# Power_Supply.net
KiCad netlist of a schematic drawn in Altium Designer
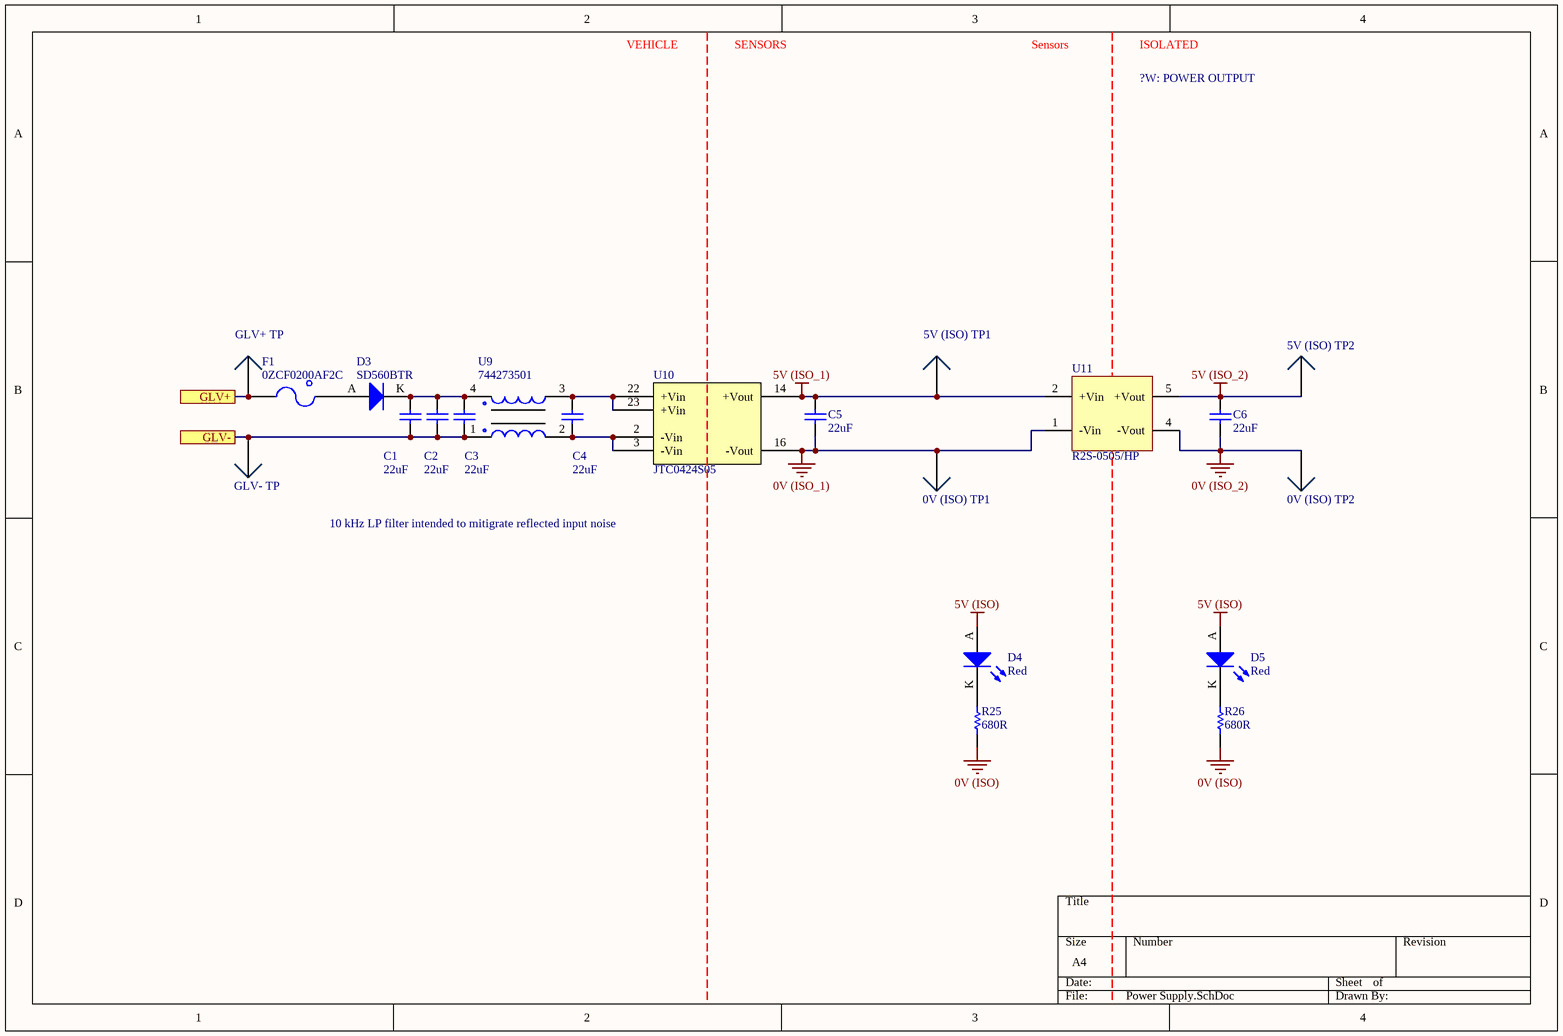
[diagram p0: Power Supply.SchDoc]

(export (version "E")
  (design (tool "Eeschema 10.0.6"))
  (components
    (comp (ref "0V (ISO) TP1")
      (value "0mm")
      (footprint "SMD Test Point")
      (fields (field (name "PART NUMBER") "SMD Test Point") (field (name "CONTACT") "NA"))
      (libsource (lib "ts_20-standard-connectors") (part "Test Point"))
    )
    (comp (ref "0V (ISO) TP2")
      (value "0mm")
      (footprint "SMD Test Point")
      (fields (field (name "PART NUMBER") "SMD Test Point") (field (name "CONTACT") "NA"))
      (libsource (lib "ts_20-standard-connectors") (part "Test Point"))
    )
    (comp (ref "5V (ISO) TP1")
      (value "0mm")
      (footprint "SMD Test Point")
      (fields (field (name "PART NUMBER") "SMD Test Point") (field (name "CONTACT") "NA"))
      (libsource (lib "ts_20-standard-connectors") (part "Test Point"))
    )
    (comp (ref "5V (ISO) TP2")
      (value "0mm")
      (footprint "SMD Test Point")
      (fields (field (name "PART NUMBER") "SMD Test Point") (field (name "CONTACT") "NA"))
      (libsource (lib "ts_20-standard-connectors") (part "Test Point"))
    )
    (comp (ref "C1")
      (value "22uF")
      (footprint "1206")
      (fields
        (field (name "PART NUMBER") "CC1206MKX5R7BB226")
        (field (name "TOLERANCE") "20%")
        (field (name "MANUFACTURER") "YAGEO")
      )
      (libsource (lib "ts_20-standard-library") (part "Capacitor"))
    )
    (comp (ref "C2")
      (value "22uF")
      (footprint "1206")
      (fields
        (field (name "PART NUMBER") "CC1206MKX5R7BB226")
        (field (name "TOLERANCE") "20%")
        (field (name "MANUFACTURER") "YAGEO")
      )
      (libsource (lib "ts_20-standard-library") (part "Capacitor"))
    )
    (comp (ref "C3")
      (value "22uF")
      (footprint "1206")
      (fields
        (field (name "PART NUMBER") "CC1206MKX5R7BB226")
        (field (name "TOLERANCE") "20%")
        (field (name "MANUFACTURER") "YAGEO")
      )
      (libsource (lib "ts_20-standard-library") (part "Capacitor"))
    )
    (comp (ref "C4")
      (value "22uF")
      (footprint "1206")
      (fields
        (field (name "PART NUMBER") "CC1206MKX5R7BB226")
        (field (name "TOLERANCE") "20%")
        (field (name "MANUFACTURER") "YAGEO")
      )
      (libsource (lib "ts_20-standard-library") (part "Capacitor"))
    )
    (comp (ref "C5")
      (value "22uF")
      (footprint "1206")
      (fields
        (field (name "PART NUMBER") "CC1206MKX5R7BB226")
        (field (name "TOLERANCE") "20%")
        (field (name "MANUFACTURER") "YAGEO")
      )
      (libsource (lib "ts_20-standard-library") (part "Capacitor"))
    )
    (comp (ref "C6")
      (value "22uF")
      (footprint "1206")
      (fields
        (field (name "PART NUMBER") "CC1206MKX5R7BB226")
        (field (name "TOLERANCE") "20%")
        (field (name "MANUFACTURER") "YAGEO")
      )
      (libsource (lib "ts_20-standard-library") (part "Capacitor"))
    )
    (comp (ref "D3")
      (value "SD560BTR")
      (footprint "SMB Diode")
      (description "1.2V_F 600V 5A SMB")
      (fields
        (field (name "MANUFACTURER") "SMC Diode Solutions")
        (field (name "DIGIKEY PART NUMBER") "1655-1530-2-ND")
      )
      (libsource (lib "ts_20-standard-library") (part "Diode"))
    )
    (comp (ref "D4")
      (value "Red")
      (footprint "0805 LED")
      (description "Red LED Indication - Discrete 1.75V 0805 (2012 Metric)")
      (fields (field (name "PART NUMBER") "SML-210LTT86") (field (name "MANUFACTURER") "ROHM Semiconductor"))
      (libsource (lib "ts_20-standard-library") (part "LED"))
    )
    (comp (ref "D5")
      (value "Red")
      (footprint "0805 LED")
      (description "Red LED Indication - Discrete 1.75V 0805 (2012 Metric)")
      (fields (field (name "PART NUMBER") "SML-210LTT86") (field (name "MANUFACTURER") "ROHM Semiconductor"))
      (libsource (lib "ts_20-standard-library") (part "LED"))
    )
    (comp (ref "F1")
      (value "0ZCF0200AF2C")
      (footprint "2920")
      (description "SMD 24V 2A Fuse")
      (fields
        (field (name "MANUFACTURER") "Bel Fuse Inc")
        (field (name "DIGIKEY PART NUMBER") "507-1749-2-ND")
      )
      (libsource (lib "ts_20-standard-library") (part "PTC Fuse"))
    )
    (comp (ref "GLV+ TP")
      (value "0mm")
      (footprint "SMD Test Point")
      (fields (field (name "PART NUMBER") "SMD Test Point") (field (name "CONTACT") "NA"))
      (libsource (lib "ts_20-standard-connectors") (part "Test Point"))
    )
    (comp (ref "GLV- TP")
      (value "0mm")
      (footprint "SMD Test Point")
      (fields (field (name "PART NUMBER") "SMD Test Point") (field (name "CONTACT") "NA"))
      (libsource (lib "ts_20-standard-connectors") (part "Test Point"))
    )
    (comp (ref "R25")
      (value "680R")
      (footprint "0805")
      (fields
        (field (name "PART NUMBER") "RC0805FR07680RL")
        (field (name "MANUFACTURER") "YAGEO")
        (field (name "TOLERANCE") "0.01")
      )
      (libsource (lib "ts_20-standard-library") (part "Resistor"))
    )
    (comp (ref "R26")
      (value "680R")
      (footprint "0805")
      (fields
        (field (name "PART NUMBER") "RC0805FR07680RL")
        (field (name "MANUFACTURER") "YAGEO")
        (field (name "TOLERANCE") "0.01")
      )
      (libsource (lib "ts_20-standard-library") (part "Resistor"))
    )
    (comp (ref "U9")
      (value "744273501")
      (footprint "Wurth 4-PC Pad")
      (description "5µH @ 100kHz 2 Line Common Mode Choke Surface Mount 500 Ohms @ 130MHz 5A DCR 5.5mOhm")
      (fields
        (field (name "MANUFACTURER") "Wurth Electronics Inc")
        (field (name "DIGIKEY PART NUMBER") "732-2214-6-ND")
      )
      (libsource (lib "ts_20-standard-library") (part "744273501"))
    )
    (comp (ref "U10")
      (value "JTC0424S05")
      (footprint "24-DIP Module, 7 Leads")
      (description "DC DC CONVERTER 5V 4W")
      (fields (field (name "MANUFACTURER") "XP Power") (field (name "DIGIKEY PART NUMBER") "JTC0424S05-ND"))
      (libsource (lib "ts_20-standard-library") (part "JTC0424S05"))
    )
    (comp (ref "U11")
      (value "R2S-0505/HP")
      (footprint "RECOM 8-SMD (5 Pin)")
      (description "Isolated Module DC DC Converter 1 Output 3.3V 606mA 4.5V - 5.5V Input")
      (fields (field (name "MANUFACTURER") "Recom") (field (name "DIGIKEY PART NUMBER") "945-1764-5-ND"))
      (libsource (lib "ts_20-standard-library") (part "R2S-0505/HP"))
    )
  )
  (nets
    (net (code "1") (name "/GLV+") (class "Default")
      (node (ref "F1") (pin "1") (pinfunction "1_1") (pintype "passive"))
      (node (ref "GLV+ TP") (pin "1") (pinfunction "1_1") (pintype "passive"))
    )
    (net (code "2") (name "/GLV-") (class "Default")
      (node (ref "C1") (pin "1") (pinfunction "1_1") (pintype "passive"))
      (node (ref "C2") (pin "1") (pinfunction "1_1") (pintype "passive"))
      (node (ref "C3") (pin "1") (pinfunction "1_1") (pintype "passive"))
      (node (ref "GLV- TP") (pin "1") (pinfunction "1_1") (pintype "passive"))
      (node (ref "U9") (pin "1") (pinfunction "1_1") (pintype "passive"))
    )
    (net (code "3") (name "0V (ISO)") (class "Default")
      (node (ref "R25") (pin "1") (pinfunction "1_1") (pintype "passive"))
      (node (ref "R26") (pin "1") (pinfunction "1_1") (pintype "passive"))
    )
    (net (code "4") (name "0V (ISO_1)") (class "Default")
      (node (ref "0V (ISO) TP1") (pin "1") (pinfunction "1_1") (pintype "passive"))
      (node (ref "C5") (pin "1") (pinfunction "1_1") (pintype "passive"))
      (node (ref "U10") (pin "16") (pinfunction "-Vout_16") (pintype "passive"))
      (node (ref "U11") (pin "1") (pinfunction "-Vin_1") (pintype "power_in"))
    )
    (net (code "5") (name "0V (ISO_2)") (class "Default")
      (node (ref "0V (ISO) TP2") (pin "1") (pinfunction "1_1") (pintype "passive"))
      (node (ref "C6") (pin "1") (pinfunction "1_1") (pintype "passive"))
      (node (ref "U11") (pin "4") (pinfunction "-Vout_4") (pintype "power_in"))
    )
    (net (code "6") (name "5V (ISO)") (class "Default")
      (node (ref "D4") (pin "A") (pinfunction "A_A") (pintype "passive"))
      (node (ref "D5") (pin "A") (pinfunction "A_A") (pintype "passive"))
    )
    (net (code "7") (name "5V (ISO_1)") (class "Default")
      (node (ref "5V (ISO) TP1") (pin "1") (pinfunction "1_1") (pintype "passive"))
      (node (ref "C5") (pin "2") (pinfunction "2_2") (pintype "passive"))
      (node (ref "U10") (pin "14") (pinfunction "+Vout_14") (pintype "passive"))
      (node (ref "U11") (pin "2") (pinfunction "+Vin_2") (pintype "power_in"))
    )
    (net (code "8") (name "5V (ISO_2)") (class "Default")
      (node (ref "5V (ISO) TP2") (pin "1") (pinfunction "1_1") (pintype "passive"))
      (node (ref "C6") (pin "2") (pinfunction "2_2") (pintype "passive"))
      (node (ref "U11") (pin "5") (pinfunction "+Vout_5") (pintype "power_in"))
    )
    (net (code "9") (name "Net-(C1-Pad2)") (class "Default")
      (node (ref "C1") (pin "2") (pinfunction "2_2") (pintype "passive"))
      (node (ref "C2") (pin "2") (pinfunction "2_2") (pintype "passive"))
      (node (ref "C3") (pin "2") (pinfunction "2_2") (pintype "passive"))
      (node (ref "D3") (pin "K") (pinfunction "K_K") (pintype "passive"))
      (node (ref "U9") (pin "4") (pinfunction "4_4") (pintype "passive"))
    )
    (net (code "10") (name "Net-(C4-Pad1)") (class "Default")
      (node (ref "C4") (pin "1") (pinfunction "1_1") (pintype "passive"))
      (node (ref "U10") (pin "2") (pinfunction "-Vin_2") (pintype "passive"))
      (node (ref "U10") (pin "3") (pinfunction "-Vin_3") (pintype "passive"))
      (node (ref "U9") (pin "2") (pinfunction "2_2") (pintype "passive"))
    )
    (net (code "11") (name "Net-(C4-Pad2)") (class "Default")
      (node (ref "C4") (pin "2") (pinfunction "2_2") (pintype "passive"))
      (node (ref "U10") (pin "22") (pinfunction "+Vin_22") (pintype "passive"))
      (node (ref "U10") (pin "23") (pinfunction "+Vin_23") (pintype "passive"))
      (node (ref "U9") (pin "3") (pinfunction "3_3") (pintype "power_in"))
    )
    (net (code "12") (name "Net-(D3-PadA)") (class "Default")
      (node (ref "D3") (pin "A") (pinfunction "A_A") (pintype "passive"))
      (node (ref "F1") (pin "2") (pinfunction "2_2") (pintype "passive"))
    )
    (net (code "13") (name "Net-(D4-PadK)") (class "Default")
      (node (ref "D4") (pin "K") (pinfunction "K_K") (pintype "passive"))
      (node (ref "R25") (pin "2") (pinfunction "2_2") (pintype "passive"))
    )
    (net (code "14") (name "Net-(D5-PadK)") (class "Default")
      (node (ref "D5") (pin "K") (pinfunction "K_K") (pintype "passive"))
      (node (ref "R26") (pin "2") (pinfunction "2_2") (pintype "passive"))
    )
  )
)
